# lab1_sokolov_usb_i2c.net
KiCad netlist of a schematic drawn in Altium Designer
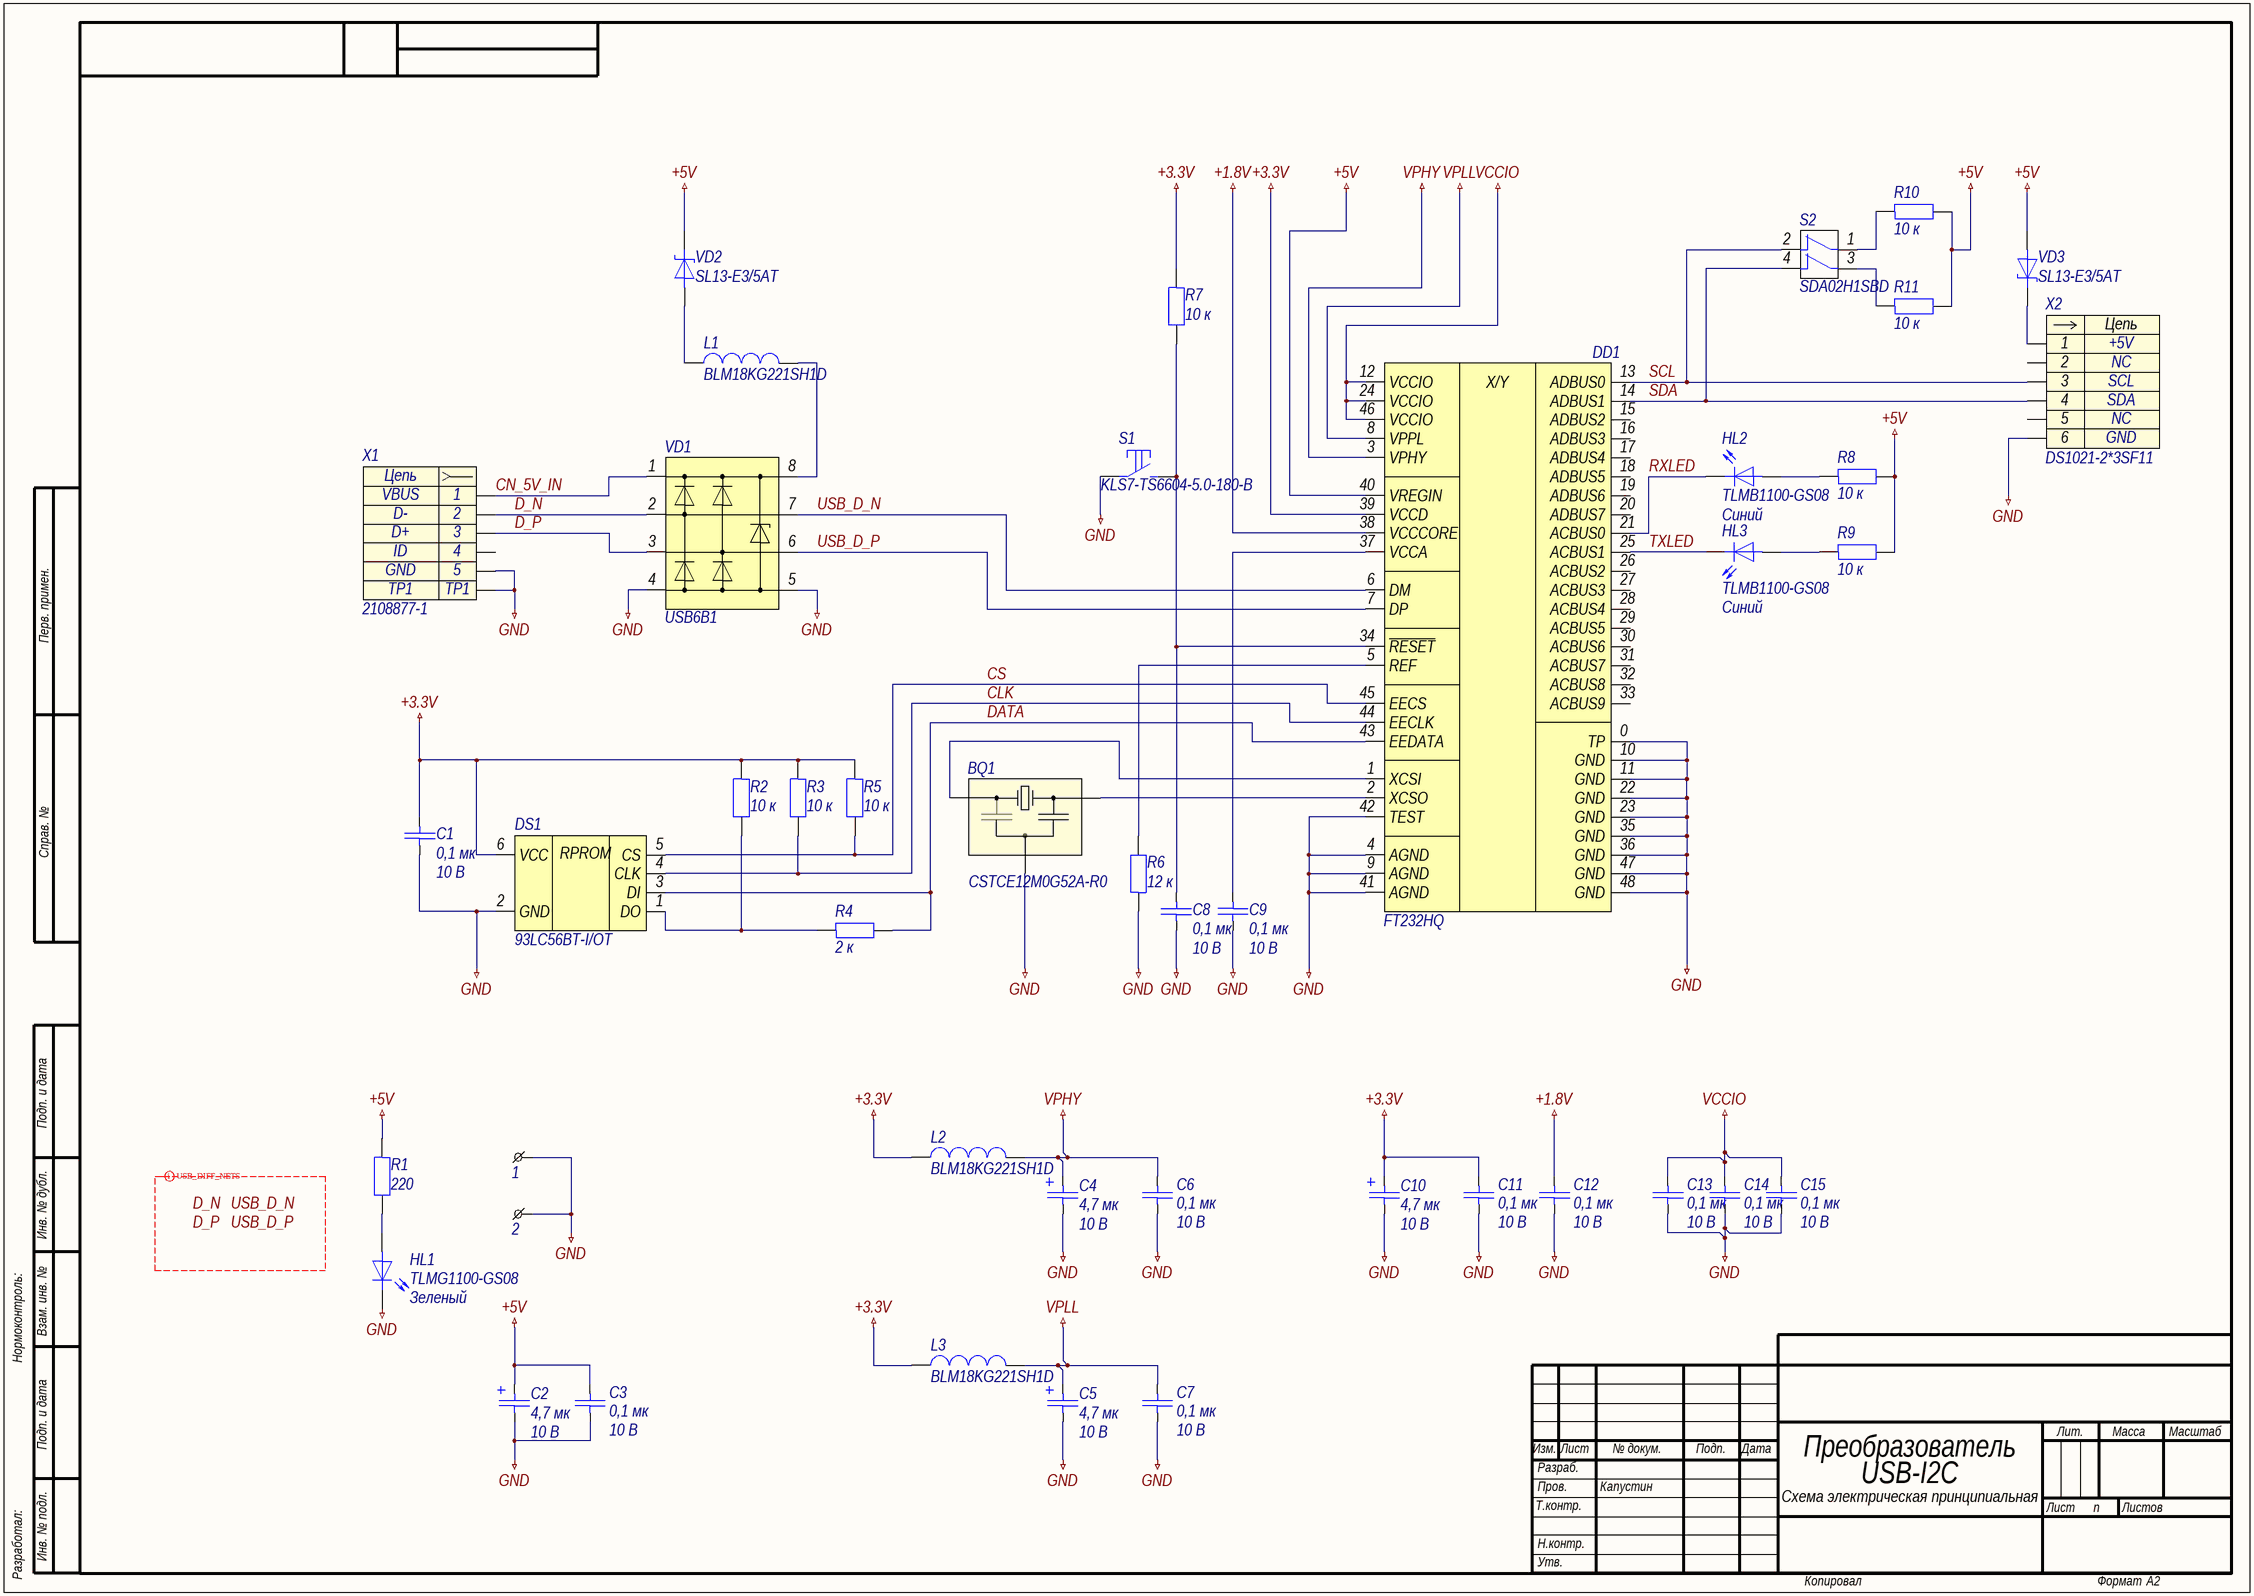
[diagram p0: lab1_sokolov_usb_i2c.SchDoc]

(export (version "E")
  (design (tool "Eeschema 10.0.6"))
  (components
    (comp (ref "1")
      (value "MOUNTING_HOLE")
      (footprint "HOLE_1,6X3,3")
      (libsource (lib "lab1_kapustin_usb_spi") (part "Отверстие 1,6x3,3"))
    )
    (comp (ref "2")
      (value "MOUNTING_HOLE")
      (footprint "HOLE_1,6X3,3")
      (libsource (lib "lab1_kapustin_usb_spi") (part "Отверстие 1,6x3,3"))
    )
    (comp (ref "BQ1")
      (value "CSTCE12M0G52A-R0")
      (footprint "CSTCE-3-320X130X70")
      (description "=Описание")
      (libsource (lib "Database_Students") (part "CSTCE12M0G52A-R0"))
    )
    (comp (ref "C1")
      (value "0,1 мк")
      (footprint "C0603")
      (description "=Описание")
      (fields (field (name "НАПРЯЖЕНИЕ") "10 В"))
      (libsource (lib "Database_Students") (part "CAPACITOR-NONPOLAR"))
    )
    (comp (ref "C2")
      (value "4,7 мк")
      (footprint "C3216-18")
      (description "=Описание")
      (fields (field (name "НАПРЯЖЕНИЕ") "10 В"))
      (libsource (lib "Database_Students") (part "CAPACITOR-POLAR"))
    )
    (comp (ref "C3")
      (value "0,1 мк")
      (footprint "C0603")
      (description "=Описание")
      (fields (field (name "НАПРЯЖЕНИЕ") "10 В"))
      (libsource (lib "Database_Students") (part "CAPACITOR-NONPOLAR"))
    )
    (comp (ref "C4")
      (value "4,7 мк")
      (footprint "C3216-18")
      (description "=Описание")
      (fields (field (name "НАПРЯЖЕНИЕ") "10 В"))
      (libsource (lib "Database_Students") (part "CAPACITOR-POLAR"))
    )
    (comp (ref "C5")
      (value "4,7 мк")
      (footprint "C3216-18")
      (description "=Описание")
      (fields (field (name "НАПРЯЖЕНИЕ") "10 В"))
      (libsource (lib "Database_Students") (part "CAPACITOR-POLAR"))
    )
    (comp (ref "C6")
      (value "0,1 мк")
      (footprint "C0603")
      (description "=Описание")
      (fields (field (name "НАПРЯЖЕНИЕ") "10 В"))
      (libsource (lib "Database_Students") (part "CAPACITOR-NONPOLAR"))
    )
    (comp (ref "C7")
      (value "0,1 мк")
      (footprint "C0603")
      (description "=Описание")
      (fields (field (name "НАПРЯЖЕНИЕ") "10 В"))
      (libsource (lib "Database_Students") (part "CAPACITOR-NONPOLAR"))
    )
    (comp (ref "C8")
      (value "0,1 мк")
      (footprint "C0603")
      (description "=Описание")
      (fields (field (name "НАПРЯЖЕНИЕ") "10 В"))
      (libsource (lib "Database_Students") (part "CAPACITOR-NONPOLAR"))
    )
    (comp (ref "C9")
      (value "0,1 мк")
      (footprint "C0603")
      (description "=Описание")
      (fields (field (name "НАПРЯЖЕНИЕ") "10 В"))
      (libsource (lib "Database_Students") (part "CAPACITOR-NONPOLAR"))
    )
    (comp (ref "C10")
      (value "4,7 мк")
      (footprint "C3216-18")
      (description "=Описание")
      (fields (field (name "НАПРЯЖЕНИЕ") "10 В"))
      (libsource (lib "Database_Students") (part "CAPACITOR-POLAR"))
    )
    (comp (ref "C11")
      (value "0,1 мк")
      (footprint "C0603")
      (description "=Описание")
      (fields (field (name "НАПРЯЖЕНИЕ") "10 В"))
      (libsource (lib "Database_Students") (part "CAPACITOR-NONPOLAR"))
    )
    (comp (ref "C12")
      (value "0,1 мк")
      (footprint "C0603")
      (description "=Описание")
      (fields (field (name "НАПРЯЖЕНИЕ") "10 В"))
      (libsource (lib "Database_Students") (part "CAPACITOR-NONPOLAR"))
    )
    (comp (ref "C13")
      (value "0,1 мк")
      (footprint "C0603")
      (description "=Описание")
      (fields (field (name "НАПРЯЖЕНИЕ") "10 В"))
      (libsource (lib "Database_Students") (part "CAPACITOR-NONPOLAR"))
    )
    (comp (ref "C14")
      (value "0,1 мк")
      (footprint "C0603")
      (description "=Описание")
      (fields (field (name "НАПРЯЖЕНИЕ") "10 В"))
      (libsource (lib "Database_Students") (part "CAPACITOR-NONPOLAR"))
    )
    (comp (ref "C15")
      (value "0,1 мк")
      (footprint "C0603")
      (description "=Описание")
      (fields (field (name "НАПРЯЖЕНИЕ") "10 В"))
      (libsource (lib "Database_Students") (part "CAPACITOR-NONPOLAR"))
    )
    (comp (ref "DD1")
      (value "FT232HQ")
      (footprint "QFN-48-800X800X90")
      (description "=Описание")
      (libsource (lib "Database_Students") (part "FT232HQ"))
    )
    (comp (ref "DS1")
      (value "93LC56BT-I/OT")
      (footprint "SOT-23-6")
      (description "=Описание")
      (libsource (lib "Database_Students") (part "93LC56BT-I/OT"))
    )
    (comp (ref "HL1")
      (value "TLMG1100-GS08")
      (footprint "HL0603")
      (description "=Описание")
      (fields (field (name "COLOUR") "Зеленый"))
      (libsource (lib "Database_Students") (part "LED-COMMON"))
    )
    (comp (ref "HL2")
      (value "TLMB1100-GS08")
      (footprint "HL0603")
      (description "=Описание")
      (fields (field (name "COLOUR") "Синий"))
      (libsource (lib "Database_Students") (part "LED-COMMON"))
    )
    (comp (ref "HL3")
      (value "TLMB1100-GS08")
      (footprint "HL0603")
      (description "=Описание")
      (fields (field (name "COLOUR") "Синий"))
      (libsource (lib "Database_Students") (part "LED-COMMON"))
    )
    (comp (ref "L1")
      (value "BLM18KG221SH1D")
      (footprint "BLM-2-0603")
      (description "=Описание")
      (libsource (lib "Database_Students") (part "FERRITE-BEAD"))
    )
    (comp (ref "L2")
      (value "BLM18KG221SH1D")
      (footprint "BLM-2-0603")
      (description "=Описание")
      (libsource (lib "Database_Students") (part "FERRITE-BEAD"))
    )
    (comp (ref "L3")
      (value "BLM18KG221SH1D")
      (footprint "BLM-2-0603")
      (description "=Описание")
      (libsource (lib "Database_Students") (part "FERRITE-BEAD"))
    )
    (comp (ref "R1")
      (value "220")
      (footprint "R0603")
      (description "=Описание")
      (libsource (lib "Database_Students") (part "R-COMMON"))
    )
    (comp (ref "R2")
      (value "10 к")
      (footprint "R0603")
      (description "=Описание")
      (libsource (lib "Database_Students") (part "R-COMMON"))
    )
    (comp (ref "R3")
      (value "10 к")
      (footprint "R0603")
      (description "=Описание")
      (libsource (lib "Database_Students") (part "R-COMMON"))
    )
    (comp (ref "R4")
      (value "2 к")
      (footprint "R0603")
      (description "=Описание")
      (libsource (lib "Database_Students") (part "R-COMMON"))
    )
    (comp (ref "R5")
      (value "10 к")
      (footprint "R0603")
      (description "=Описание")
      (libsource (lib "Database_Students") (part "R-COMMON"))
    )
    (comp (ref "R6")
      (value "12 к")
      (footprint "R0603")
      (description "=Описание")
      (libsource (lib "Database_Students") (part "RESISTOR-COMMON"))
    )
    (comp (ref "R7")
      (value "10 к")
      (footprint "R0603")
      (description "=Описание")
      (libsource (lib "Database_Students") (part "R-COMMON"))
    )
    (comp (ref "R8")
      (value "10 к")
      (footprint "R0603")
      (description "=Описание")
      (libsource (lib "Database_Students") (part "R-COMMON"))
    )
    (comp (ref "R9")
      (value "10 к")
      (footprint "R0603")
      (description "=Описание")
      (libsource (lib "Database_Students") (part "R-COMMON"))
    )
    (comp (ref "R10")
      (value "10 к")
      (footprint "R0603")
      (description "=Описание")
      (libsource (lib "Database_Students") (part "R-COMMON"))
    )
    (comp (ref "R11")
      (value "10 к")
      (footprint "R0603")
      (description "=Описание")
      (libsource (lib "Database_Students") (part "R-COMMON"))
    )
    (comp (ref "S1")
      (value "KLS7-TS6604-5.0-180-B")
      (footprint "KLS7-TS6604-5.0-180-B")
      (description "=Описание")
      (libsource (lib "Database_Students") (part "BUTTON"))
    )
    (comp (ref "S2")
      (value "SDA02H1SBD")
      (footprint "SDA02H1SBD")
      (description "=Описание")
      (libsource (lib "Database_Students") (part "SWITCH-4C"))
    )
    (comp (ref "VD1")
      (value "USB6B1")
      (footprint "SO-8")
      (description "=Описание")
      (libsource (lib "Database_Students") (part "USB6B1"))
    )
    (comp (ref "VD2")
      (value "SL13-E3/5AT")
      (footprint "DO-214AC")
      (description "=Описание")
      (libsource (lib "Database_Students") (part "DIODE-SCHOTTKY"))
    )
    (comp (ref "VD3")
      (value "SL13-E3/5AT")
      (footprint "DO-214AC")
      (description "=Описание")
      (libsource (lib "Database_Students") (part "DIODE-SCHOTTKY"))
    )
    (comp (ref "X1")
      (value "2108877-1")
      (footprint "2108877-1")
      (libsource (lib "2108877-1_micro_usb-b") (part "2108877-1_micro_usb-b"))
    )
    (comp (ref "X2")
      (value "DS1021-2*3SF11")
      (footprint "DS1021-2X3SF11")
      (description "=Описание")
      (libsource (lib "Database_Students") (part "HEADER-6-PLG"))
    )
  )
  (nets
    (net (code "1") (name "+1.8V") (class "Default")
      (node (ref "C12") (pin "1") (pinfunction "1_1") (pintype "passive"))
      (node (ref "DD1") (pin "38") (pinfunction "VCCCORE_38") (pintype "passive"))
    )
    (net (code "2") (name "+3.3V") (class "Default")
      (node (ref "C1") (pin "1") (pinfunction "1_1") (pintype "passive"))
      (node (ref "C10") (pin "1") (pinfunction "1_1") (pintype "passive"))
      (node (ref "C11") (pin "1") (pinfunction "1_1") (pintype "passive"))
      (node (ref "DD1") (pin "39") (pinfunction "VCCD_39") (pintype "passive"))
      (node (ref "DS1") (pin "6") (pinfunction "VCC_6") (pintype "passive"))
      (node (ref "L2") (pin "1") (pinfunction "1_1") (pintype "passive"))
      (node (ref "L3") (pin "1") (pinfunction "1_1") (pintype "passive"))
      (node (ref "R2") (pin "1") (pinfunction "1_1") (pintype "passive"))
      (node (ref "R3") (pin "1") (pinfunction "1_1") (pintype "passive"))
      (node (ref "R5") (pin "1") (pinfunction "1_1") (pintype "passive"))
      (node (ref "R7") (pin "1") (pinfunction "1_1") (pintype "passive"))
    )
    (net (code "3") (name "+5V") (class "Default")
      (node (ref "C2") (pin "1") (pinfunction "1_1") (pintype "passive"))
      (node (ref "C3") (pin "1") (pinfunction "1_1") (pintype "passive"))
      (node (ref "DD1") (pin "40") (pinfunction "VREGIN_40") (pintype "passive"))
      (node (ref "R1") (pin "1") (pinfunction "1_1") (pintype "passive"))
      (node (ref "R10") (pin "2") (pinfunction "2_2") (pintype "passive"))
      (node (ref "R11") (pin "2") (pinfunction "2_2") (pintype "passive"))
      (node (ref "R8") (pin "2") (pinfunction "2_2") (pintype "passive"))
      (node (ref "R9") (pin "2") (pinfunction "2_2") (pintype "passive"))
      (node (ref "VD2") (pin "1") (pinfunction "1_1") (pintype "passive"))
      (node (ref "VD3") (pin "2") (pinfunction "2_2") (pintype "passive"))
    )
    (net (code "4") (name "/CLK") (class "Default")
      (node (ref "DD1") (pin "44") (pinfunction "EECLK_44") (pintype "passive"))
      (node (ref "DS1") (pin "4") (pinfunction "CLK_4") (pintype "passive"))
      (node (ref "R3") (pin "2") (pinfunction "2_2") (pintype "passive"))
    )
    (net (code "5") (name "/CN_5V_IN") (class "Default")
      (node (ref "VD1") (pin "1") (pinfunction "1_1") (pintype "passive"))
      (node (ref "X1") (pin "1") (pinfunction "1_1") (pintype "passive"))
    )
    (net (code "6") (name "/CS") (class "Default")
      (node (ref "DD1") (pin "45") (pinfunction "EECS_45") (pintype "passive"))
      (node (ref "DS1") (pin "5") (pinfunction "CS_5") (pintype "passive"))
      (node (ref "R5") (pin "2") (pinfunction "2_2") (pintype "passive"))
    )
    (net (code "7") (name "/DATA") (class "Default")
      (node (ref "DD1") (pin "43") (pinfunction "EEDATA_43") (pintype "passive"))
      (node (ref "DS1") (pin "3") (pinfunction "DI_3") (pintype "passive"))
      (node (ref "R4") (pin "2") (pinfunction "2_2") (pintype "passive"))
    )
    (net (code "8") (name "/D_N") (class "Default")
      (node (ref "VD1") (pin "2") (pinfunction "2_2") (pintype "passive"))
      (node (ref "X1") (pin "2") (pinfunction "2_2") (pintype "passive"))
    )
    (net (code "9") (name "/D_P") (class "Default")
      (node (ref "VD1") (pin "3") (pinfunction "3_3") (pintype "passive"))
      (node (ref "X1") (pin "3") (pinfunction "3_3") (pintype "passive"))
    )
    (net (code "10") (name "/RXLED") (class "Default")
      (node (ref "DD1") (pin "21") (pinfunction "ACBUS0_21") (pintype "passive"))
      (node (ref "HL2") (pin "1") (pinfunction "1_1") (pintype "passive"))
    )
    (net (code "11") (name "/SCL") (class "Default")
      (node (ref "DD1") (pin "13") (pinfunction "ADBUS0_13") (pintype "passive"))
      (node (ref "S2") (pin "2") (pinfunction "2_2") (pintype "passive"))
      (node (ref "X2") (pin "3") (pinfunction "3_3") (pintype "passive"))
    )
    (net (code "12") (name "/SDA") (class "Default")
      (node (ref "DD1") (pin "14") (pinfunction "ADBUS1_14") (pintype "passive"))
      (node (ref "S2") (pin "4") (pinfunction "4_4") (pintype "passive"))
      (node (ref "X2") (pin "4") (pinfunction "4_4") (pintype "passive"))
    )
    (net (code "13") (name "/TXLED") (class "Default")
      (node (ref "DD1") (pin "25") (pinfunction "ACBUS1_25") (pintype "passive"))
      (node (ref "HL3") (pin "1") (pinfunction "1_1") (pintype "passive"))
    )
    (net (code "14") (name "/USB_D_N") (class "Default")
      (node (ref "DD1") (pin "6") (pinfunction "DM_6") (pintype "passive"))
      (node (ref "VD1") (pin "7") (pinfunction "7_7") (pintype "passive"))
    )
    (net (code "15") (name "/USB_D_P") (class "Default")
      (node (ref "DD1") (pin "7") (pinfunction "DP_7") (pintype "passive"))
      (node (ref "VD1") (pin "6") (pinfunction "6_6") (pintype "passive"))
    )
    (net (code "16") (name "GND") (class "Default")
      (node (ref "1") (pin "1") (pinfunction "1_1") (pintype "passive"))
      (node (ref "2") (pin "1") (pinfunction "1_1") (pintype "passive"))
      (node (ref "BQ1") (pin "2") (pinfunction "2_2") (pintype "passive"))
      (node (ref "C1") (pin "2") (pinfunction "2_2") (pintype "passive"))
      (node (ref "C10") (pin "2") (pinfunction "2_2") (pintype "passive"))
      (node (ref "C11") (pin "2") (pinfunction "2_2") (pintype "passive"))
      (node (ref "C12") (pin "2") (pinfunction "2_2") (pintype "passive"))
      (node (ref "C13") (pin "2") (pinfunction "2_2") (pintype "passive"))
      (node (ref "C14") (pin "2") (pinfunction "2_2") (pintype "passive"))
      (node (ref "C15") (pin "2") (pinfunction "2_2") (pintype "passive"))
      (node (ref "C2") (pin "2") (pinfunction "2_2") (pintype "passive"))
      (node (ref "C3") (pin "2") (pinfunction "2_2") (pintype "passive"))
      (node (ref "C4") (pin "2") (pinfunction "2_2") (pintype "passive"))
      (node (ref "C5") (pin "2") (pinfunction "2_2") (pintype "passive"))
      (node (ref "C6") (pin "2") (pinfunction "2_2") (pintype "passive"))
      (node (ref "C7") (pin "2") (pinfunction "2_2") (pintype "passive"))
      (node (ref "C8") (pin "2") (pinfunction "2_2") (pintype "passive"))
      (node (ref "C9") (pin "1") (pinfunction "1_1") (pintype "passive"))
      (node (ref "DD1") (pin "0") (pinfunction "TP_0") (pintype "passive"))
      (node (ref "DD1") (pin "10") (pinfunction "GND_10") (pintype "passive"))
      (node (ref "DD1") (pin "11") (pinfunction "GND_11") (pintype "passive"))
      (node (ref "DD1") (pin "22") (pinfunction "GND_22") (pintype "passive"))
      (node (ref "DD1") (pin "23") (pinfunction "GND_23") (pintype "passive"))
      (node (ref "DD1") (pin "35") (pinfunction "GND_35") (pintype "passive"))
      (node (ref "DD1") (pin "36") (pinfunction "GND_36") (pintype "passive"))
      (node (ref "DD1") (pin "4") (pinfunction "AGND_4") (pintype "passive"))
      (node (ref "DD1") (pin "41") (pinfunction "AGND_41") (pintype "passive"))
      (node (ref "DD1") (pin "42") (pinfunction "TEST_42") (pintype "passive"))
      (node (ref "DD1") (pin "47") (pinfunction "GND_47") (pintype "passive"))
      (node (ref "DD1") (pin "48") (pinfunction "GND_48") (pintype "passive"))
      (node (ref "DD1") (pin "9") (pinfunction "AGND_9") (pintype "passive"))
      (node (ref "DS1") (pin "2") (pinfunction "GND_2") (pintype "passive"))
      (node (ref "HL1") (pin "1") (pinfunction "1_1") (pintype "passive"))
      (node (ref "R6") (pin "1") (pinfunction "1_1") (pintype "passive"))
      (node (ref "S1") (pin "1") (pinfunction "1_1") (pintype "passive"))
      (node (ref "VD1") (pin "4") (pinfunction "4_4") (pintype "passive"))
      (node (ref "VD1") (pin "5") (pinfunction "5_5") (pintype "passive"))
      (node (ref "X1") (pin "5") (pinfunction "5_5") (pintype "passive"))
      (node (ref "X1") (pin "TP1") (pinfunction "TP1_TP1") (pintype "passive"))
      (node (ref "X2") (pin "6") (pinfunction "6_6") (pintype "passive"))
    )
    (net (code "17") (name "Net-(DD1-REF)") (class "Default")
      (node (ref "DD1") (pin "5") (pinfunction "REF_5") (pintype "passive"))
      (node (ref "R6") (pin "2") (pinfunction "2_2") (pintype "passive"))
    )
    (net (code "18") (name "Net-(DD1-VCCA)") (class "Default")
      (node (ref "C9") (pin "2") (pinfunction "2_2") (pintype "passive"))
      (node (ref "DD1") (pin "37") (pinfunction "VCCA_37") (pintype "passive"))
    )
    (net (code "19") (name "Net-(DD1-XCSI)") (class "Default")
      (node (ref "BQ1") (pin "3") (pinfunction "3_3") (pintype "passive"))
      (node (ref "DD1") (pin "1") (pinfunction "XCSI_1") (pintype "passive"))
    )
    (net (code "20") (name "Net-(DD1-XCSO)") (class "Default")
      (node (ref "BQ1") (pin "1") (pinfunction "1_1") (pintype "passive"))
      (node (ref "DD1") (pin "2") (pinfunction "XCSO_2") (pintype "passive"))
    )
    (net (code "21") (name "Net-(DD1-~{RESET})") (class "Default")
      (node (ref "C8") (pin "1") (pinfunction "1_1") (pintype "passive"))
      (node (ref "DD1") (pin "34") (pinfunction "~{RESET}_34") (pintype "passive"))
      (node (ref "R7") (pin "2") (pinfunction "2_2") (pintype "passive"))
      (node (ref "S1") (pin "2") (pinfunction "2_2") (pintype "passive"))
    )
    (net (code "22") (name "Net-(DS1-DO)") (class "Default")
      (node (ref "DS1") (pin "1") (pinfunction "DO_1") (pintype "passive"))
      (node (ref "R2") (pin "2") (pinfunction "2_2") (pintype "passive"))
      (node (ref "R4") (pin "1") (pinfunction "1_1") (pintype "passive"))
    )
    (net (code "23") (name "Net-(HL1-Pad2)") (class "Default")
      (node (ref "HL1") (pin "2") (pinfunction "2_2") (pintype "passive"))
      (node (ref "R1") (pin "2") (pinfunction "2_2") (pintype "passive"))
    )
    (net (code "24") (name "Net-(HL2-Pad2)") (class "Default")
      (node (ref "HL2") (pin "2") (pinfunction "2_2") (pintype "passive"))
      (node (ref "R8") (pin "1") (pinfunction "1_1") (pintype "passive"))
    )
    (net (code "25") (name "Net-(HL3-Pad2)") (class "Default")
      (node (ref "HL3") (pin "2") (pinfunction "2_2") (pintype "passive"))
      (node (ref "R9") (pin "1") (pinfunction "1_1") (pintype "passive"))
    )
    (net (code "26") (name "Net-(L1-Pad1)") (class "Default")
      (node (ref "L1") (pin "1") (pinfunction "1_1") (pintype "passive"))
      (node (ref "VD2") (pin "2") (pinfunction "2_2") (pintype "passive"))
    )
    (net (code "27") (name "Net-(L1-Pad2)") (class "Default")
      (node (ref "L1") (pin "2") (pinfunction "2_2") (pintype "passive"))
      (node (ref "VD1") (pin "8") (pinfunction "8_8") (pintype "passive"))
    )
    (net (code "28") (name "Net-(R10-Pad1)") (class "Default")
      (node (ref "R10") (pin "1") (pinfunction "1_1") (pintype "passive"))
      (node (ref "S2") (pin "1") (pinfunction "1_1") (pintype "passive"))
    )
    (net (code "29") (name "Net-(R11-Pad1)") (class "Default")
      (node (ref "R11") (pin "1") (pinfunction "1_1") (pintype "passive"))
      (node (ref "S2") (pin "3") (pinfunction "3_3") (pintype "passive"))
    )
    (net (code "30") (name "Net-(VD3-Pad1)") (class "Default")
      (node (ref "VD3") (pin "1") (pinfunction "1_1") (pintype "passive"))
      (node (ref "X2") (pin "1") (pinfunction "1_1") (pintype "passive"))
    )
    (net (code "31") (name "VCCIO") (class "Default")
      (node (ref "C13") (pin "1") (pinfunction "1_1") (pintype "passive"))
      (node (ref "C14") (pin "1") (pinfunction "1_1") (pintype "passive"))
      (node (ref "C15") (pin "1") (pinfunction "1_1") (pintype "passive"))
      (node (ref "DD1") (pin "12") (pinfunction "VCCIO_12") (pintype "passive"))
      (node (ref "DD1") (pin "24") (pinfunction "VCCIO_24") (pintype "passive"))
      (node (ref "DD1") (pin "46") (pinfunction "VCCIO_46") (pintype "passive"))
    )
    (net (code "32") (name "VPHY") (class "Default")
      (node (ref "C4") (pin "1") (pinfunction "1_1") (pintype "passive"))
      (node (ref "C6") (pin "1") (pinfunction "1_1") (pintype "passive"))
      (node (ref "DD1") (pin "3") (pinfunction "VPHY_3") (pintype "passive"))
      (node (ref "L2") (pin "2") (pinfunction "2_2") (pintype "passive"))
    )
    (net (code "33") (name "VPLL") (class "Default")
      (node (ref "C5") (pin "1") (pinfunction "1_1") (pintype "passive"))
      (node (ref "C7") (pin "1") (pinfunction "1_1") (pintype "passive"))
      (node (ref "DD1") (pin "8") (pinfunction "VPPL_8") (pintype "passive"))
      (node (ref "L3") (pin "2") (pinfunction "2_2") (pintype "passive"))
    )
    (net (code "34") (name "unconnected-(DD1-ACBUS2-Pad26)") (class "Default")
      (node (ref "DD1") (pin "26") (pinfunction "ACBUS2_26") (pintype "passive"))
    )
    (net (code "35") (name "unconnected-(DD1-ACBUS3-Pad27)") (class "Default")
      (node (ref "DD1") (pin "27") (pinfunction "ACBUS3_27") (pintype "passive"))
    )
    (net (code "36") (name "unconnected-(DD1-ACBUS4-Pad28)") (class "Default")
      (node (ref "DD1") (pin "28") (pinfunction "ACBUS4_28") (pintype "passive"))
    )
    (net (code "37") (name "unconnected-(DD1-ACBUS5-Pad29)") (class "Default")
      (node (ref "DD1") (pin "29") (pinfunction "ACBUS5_29") (pintype "passive"))
    )
    (net (code "38") (name "unconnected-(DD1-ACBUS6-Pad30)") (class "Default")
      (node (ref "DD1") (pin "30") (pinfunction "ACBUS6_30") (pintype "passive"))
    )
    (net (code "39") (name "unconnected-(DD1-ACBUS7-Pad31)") (class "Default")
      (node (ref "DD1") (pin "31") (pinfunction "ACBUS7_31") (pintype "passive"))
    )
    (net (code "40") (name "unconnected-(DD1-ACBUS8-Pad32)") (class "Default")
      (node (ref "DD1") (pin "32") (pinfunction "ACBUS8_32") (pintype "passive"))
    )
    (net (code "41") (name "unconnected-(DD1-ACBUS9-Pad33)") (class "Default")
      (node (ref "DD1") (pin "33") (pinfunction "ACBUS9_33") (pintype "passive"))
    )
    (net (code "42") (name "unconnected-(DD1-ADBUS2-Pad15)") (class "Default")
      (node (ref "DD1") (pin "15") (pinfunction "ADBUS2_15") (pintype "passive"))
    )
    (net (code "43") (name "unconnected-(DD1-ADBUS3-Pad16)") (class "Default")
      (node (ref "DD1") (pin "16") (pinfunction "ADBUS3_16") (pintype "passive"))
    )
    (net (code "44") (name "unconnected-(DD1-ADBUS4-Pad17)") (class "Default")
      (node (ref "DD1") (pin "17") (pinfunction "ADBUS4_17") (pintype "passive"))
    )
    (net (code "45") (name "unconnected-(DD1-ADBUS5-Pad18)") (class "Default")
      (node (ref "DD1") (pin "18") (pinfunction "ADBUS5_18") (pintype "passive"))
    )
    (net (code "46") (name "unconnected-(DD1-ADBUS6-Pad19)") (class "Default")
      (node (ref "DD1") (pin "19") (pinfunction "ADBUS6_19") (pintype "passive"))
    )
    (net (code "47") (name "unconnected-(DD1-ADBUS7-Pad20)") (class "Default")
      (node (ref "DD1") (pin "20") (pinfunction "ADBUS7_20") (pintype "passive"))
    )
    (net (code "48") (name "unconnected-(X1-Pad4)") (class "Default")
      (node (ref "X1") (pin "4") (pinfunction "4_4") (pintype "passive"))
    )
    (net (code "49") (name "unconnected-(X2-Pad2)") (class "Default")
      (node (ref "X2") (pin "2") (pinfunction "2_2") (pintype "passive"))
    )
    (net (code "50") (name "unconnected-(X2-Pad5)") (class "Default")
      (node (ref "X2") (pin "5") (pinfunction "5_5") (pintype "passive"))
    )
  )
)
